# SWITCHES.net
KiCad netlist of a schematic drawn in Altium Designer
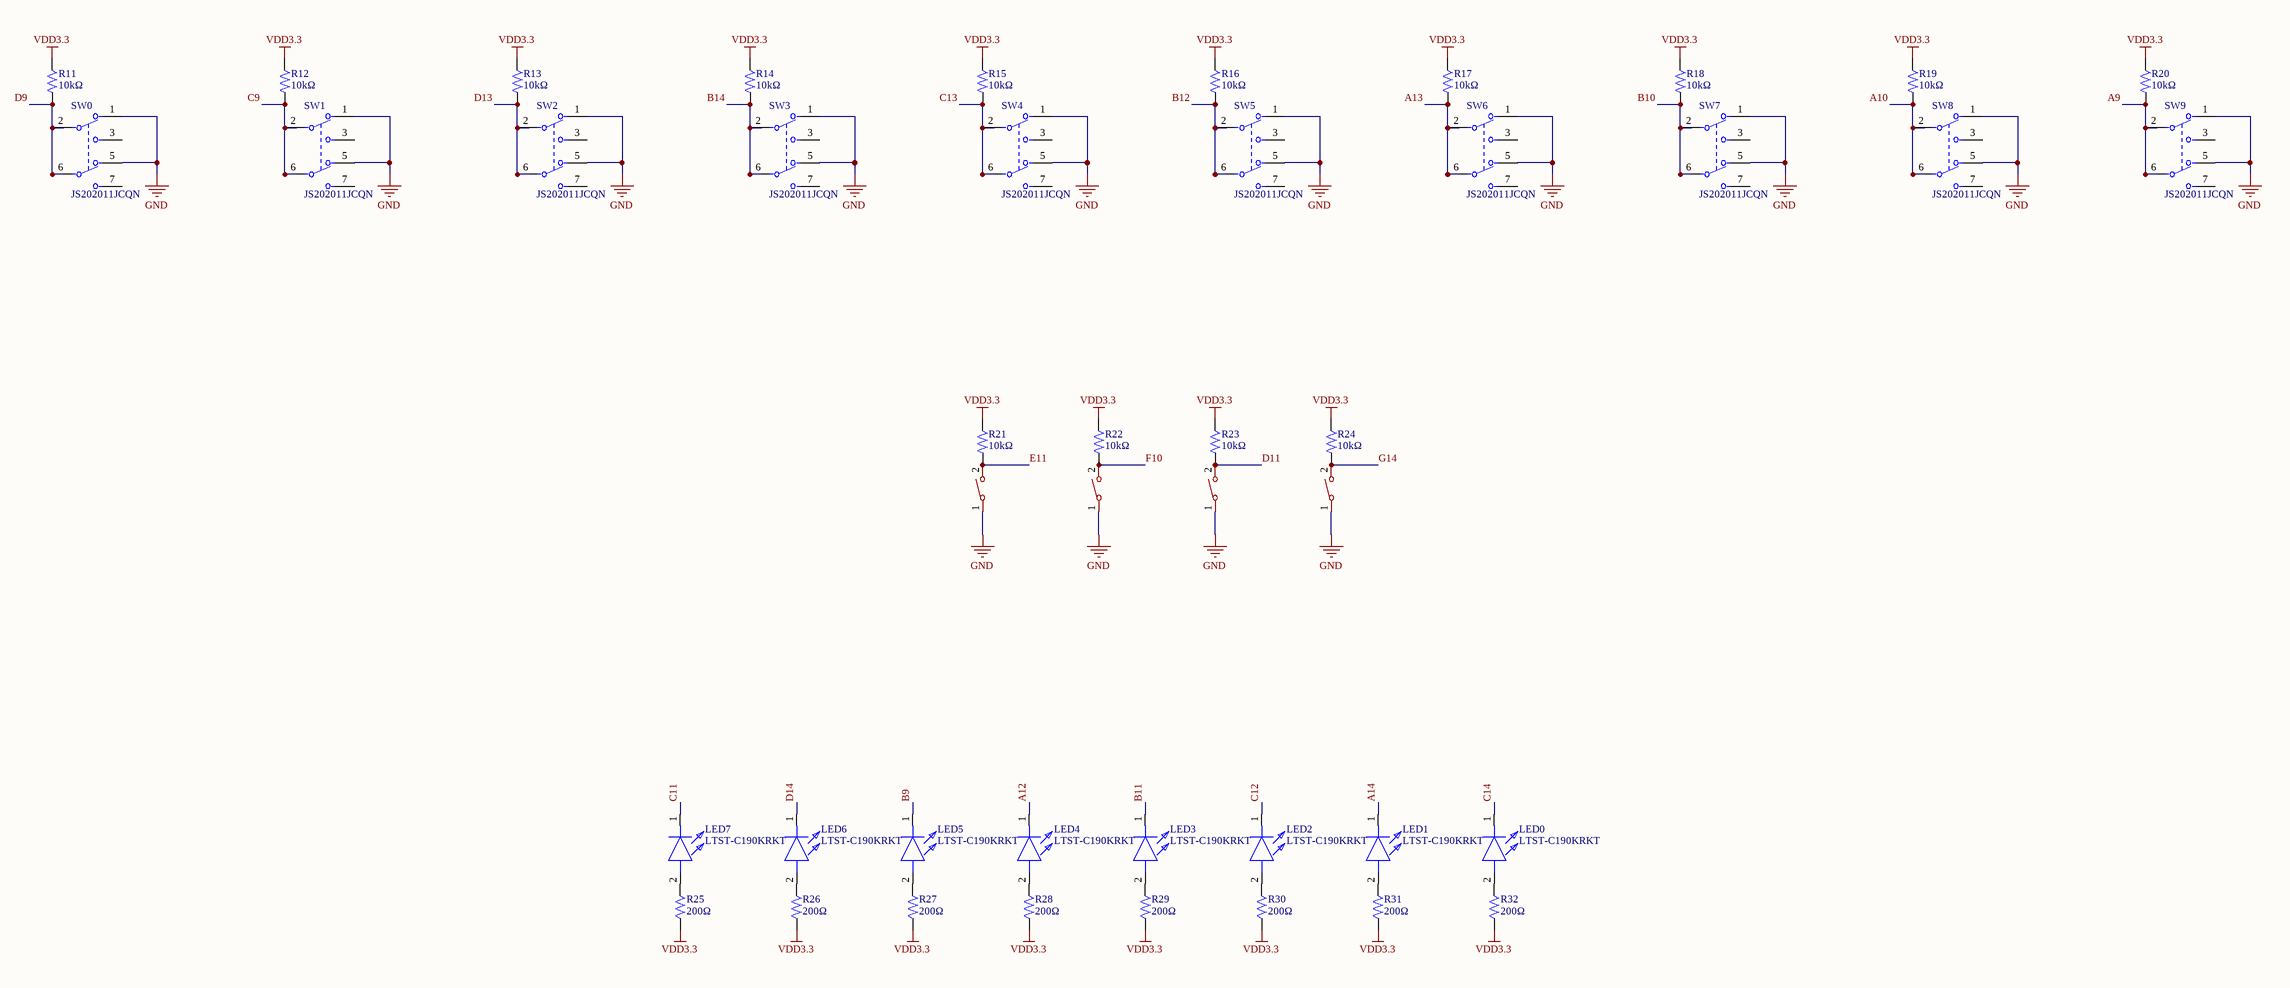
[diagram p0: SWITCHES.SchDoc]

(export (version "E")
  (design (tool "Eeschema 10.0.6"))
  (components
    (comp (ref "LED0")
      (value "LTST-C190KRKT")
      (footprint "SamacSys:LEDC1608X80N")
      (description "LED")
      (fields (field (name "MOUSER PART NUMBER") "859-LTST-C190KRKT"))
      (libsource (lib "*") (part "LTST-C190KRKT"))
    )
    (comp (ref "LED1")
      (value "LTST-C190KRKT")
      (footprint "SamacSys:LEDC1608X80N")
      (description "LED")
      (fields (field (name "MOUSER PART NUMBER") "859-LTST-C190KRKT"))
      (libsource (lib "*") (part "LTST-C190KRKT"))
    )
    (comp (ref "LED2")
      (value "LTST-C190KRKT")
      (footprint "SamacSys:LEDC1608X80N")
      (description "LED")
      (fields (field (name "MOUSER PART NUMBER") "859-LTST-C190KRKT"))
      (libsource (lib "*") (part "LTST-C190KRKT"))
    )
    (comp (ref "LED3")
      (value "LTST-C190KRKT")
      (footprint "SamacSys:LEDC1608X80N")
      (description "LED")
      (fields (field (name "MOUSER PART NUMBER") "859-LTST-C190KRKT"))
      (libsource (lib "*") (part "LTST-C190KRKT"))
    )
    (comp (ref "LED4")
      (value "LTST-C190KRKT")
      (footprint "SamacSys:LEDC1608X80N")
      (description "LED")
      (fields (field (name "MOUSER PART NUMBER") "859-LTST-C190KRKT"))
      (libsource (lib "*") (part "LTST-C190KRKT"))
    )
    (comp (ref "LED5")
      (value "LTST-C190KRKT")
      (footprint "SamacSys:LEDC1608X80N")
      (description "LED")
      (fields (field (name "MOUSER PART NUMBER") "859-LTST-C190KRKT"))
      (libsource (lib "*") (part "LTST-C190KRKT"))
    )
    (comp (ref "LED6")
      (value "LTST-C190KRKT")
      (footprint "SamacSys:LEDC1608X80N")
      (description "LED")
      (fields (field (name "MOUSER PART NUMBER") "859-LTST-C190KRKT"))
      (libsource (lib "*") (part "LTST-C190KRKT"))
    )
    (comp (ref "LED7")
      (value "LTST-C190KRKT")
      (footprint "SamacSys:LEDC1608X80N")
      (description "LED")
      (fields (field (name "MOUSER PART NUMBER") "859-LTST-C190KRKT"))
      (libsource (lib "*") (part "LTST-C190KRKT"))
    )
    (comp (ref "R11")
      (value "0603WAF1002T5E")
      (footprint "RES-0603")
      (description "Resistor, 10kΩ, ±1%, 100mW, 75V, ±100ppm/℃, -55℃~+155℃, SMD 0603")
      (fields
        (field (name "MANUFACTURER") "Uniroyal")
        (field (name "JLCPCB PART NUMBER") "C25804")
        (field (name "RESISTANCE") "10kΩ")
      )
      (libsource (lib "jlcpcb_2025_04_resistors_basic") (part "0603WAF1002T5E"))
    )
    (comp (ref "R12")
      (value "0603WAF1002T5E")
      (footprint "RES-0603")
      (description "Resistor, 10kΩ, ±1%, 100mW, 75V, ±100ppm/℃, -55℃~+155℃, SMD 0603")
      (fields
        (field (name "MANUFACTURER") "Uniroyal")
        (field (name "JLCPCB PART NUMBER") "C25804")
        (field (name "RESISTANCE") "10kΩ")
      )
      (libsource (lib "jlcpcb_2025_04_resistors_basic") (part "0603WAF1002T5E"))
    )
    (comp (ref "R13")
      (value "0603WAF1002T5E")
      (footprint "RES-0603")
      (description "Resistor, 10kΩ, ±1%, 100mW, 75V, ±100ppm/℃, -55℃~+155℃, SMD 0603")
      (fields
        (field (name "MANUFACTURER") "Uniroyal")
        (field (name "JLCPCB PART NUMBER") "C25804")
        (field (name "RESISTANCE") "10kΩ")
      )
      (libsource (lib "jlcpcb_2025_04_resistors_basic") (part "0603WAF1002T5E"))
    )
    (comp (ref "R14")
      (value "0603WAF1002T5E")
      (footprint "RES-0603")
      (description "Resistor, 10kΩ, ±1%, 100mW, 75V, ±100ppm/℃, -55℃~+155℃, SMD 0603")
      (fields
        (field (name "MANUFACTURER") "Uniroyal")
        (field (name "JLCPCB PART NUMBER") "C25804")
        (field (name "RESISTANCE") "10kΩ")
      )
      (libsource (lib "jlcpcb_2025_04_resistors_basic") (part "0603WAF1002T5E"))
    )
    (comp (ref "R15")
      (value "0603WAF1002T5E")
      (footprint "RES-0603")
      (description "Resistor, 10kΩ, ±1%, 100mW, 75V, ±100ppm/℃, -55℃~+155℃, SMD 0603")
      (fields
        (field (name "MANUFACTURER") "Uniroyal")
        (field (name "JLCPCB PART NUMBER") "C25804")
        (field (name "RESISTANCE") "10kΩ")
      )
      (libsource (lib "jlcpcb_2025_04_resistors_basic") (part "0603WAF1002T5E"))
    )
    (comp (ref "R16")
      (value "0603WAF1002T5E")
      (footprint "RES-0603")
      (description "Resistor, 10kΩ, ±1%, 100mW, 75V, ±100ppm/℃, -55℃~+155℃, SMD 0603")
      (fields
        (field (name "MANUFACTURER") "Uniroyal")
        (field (name "JLCPCB PART NUMBER") "C25804")
        (field (name "RESISTANCE") "10kΩ")
      )
      (libsource (lib "jlcpcb_2025_04_resistors_basic") (part "0603WAF1002T5E"))
    )
    (comp (ref "R17")
      (value "0603WAF1002T5E")
      (footprint "RES-0603")
      (description "Resistor, 10kΩ, ±1%, 100mW, 75V, ±100ppm/℃, -55℃~+155℃, SMD 0603")
      (fields
        (field (name "MANUFACTURER") "Uniroyal")
        (field (name "JLCPCB PART NUMBER") "C25804")
        (field (name "RESISTANCE") "10kΩ")
      )
      (libsource (lib "jlcpcb_2025_04_resistors_basic") (part "0603WAF1002T5E"))
    )
    (comp (ref "R18")
      (value "0603WAF1002T5E")
      (footprint "RES-0603")
      (description "Resistor, 10kΩ, ±1%, 100mW, 75V, ±100ppm/℃, -55℃~+155℃, SMD 0603")
      (fields
        (field (name "MANUFACTURER") "Uniroyal")
        (field (name "JLCPCB PART NUMBER") "C25804")
        (field (name "RESISTANCE") "10kΩ")
      )
      (libsource (lib "jlcpcb_2025_04_resistors_basic") (part "0603WAF1002T5E"))
    )
    (comp (ref "R19")
      (value "0603WAF1002T5E")
      (footprint "RES-0603")
      (description "Resistor, 10kΩ, ±1%, 100mW, 75V, ±100ppm/℃, -55℃~+155℃, SMD 0603")
      (fields
        (field (name "MANUFACTURER") "Uniroyal")
        (field (name "JLCPCB PART NUMBER") "C25804")
        (field (name "RESISTANCE") "10kΩ")
      )
      (libsource (lib "jlcpcb_2025_04_resistors_basic") (part "0603WAF1002T5E"))
    )
    (comp (ref "R20")
      (value "0603WAF1002T5E")
      (footprint "RES-0603")
      (description "Resistor, 10kΩ, ±1%, 100mW, 75V, ±100ppm/℃, -55℃~+155℃, SMD 0603")
      (fields
        (field (name "MANUFACTURER") "Uniroyal")
        (field (name "JLCPCB PART NUMBER") "C25804")
        (field (name "RESISTANCE") "10kΩ")
      )
      (libsource (lib "jlcpcb_2025_04_resistors_basic") (part "0603WAF1002T5E"))
    )
    (comp (ref "R21")
      (value "0603WAF1002T5E")
      (footprint "RES-0603")
      (description "Resistor, 10kΩ, ±1%, 100mW, 75V, ±100ppm/℃, -55℃~+155℃, SMD 0603")
      (fields
        (field (name "MANUFACTURER") "Uniroyal")
        (field (name "JLCPCB PART NUMBER") "C25804")
        (field (name "RESISTANCE") "10kΩ")
      )
      (libsource (lib "jlcpcb_2025_04_resistors_basic") (part "0603WAF1002T5E"))
    )
    (comp (ref "R22")
      (value "0603WAF1002T5E")
      (footprint "RES-0603")
      (description "Resistor, 10kΩ, ±1%, 100mW, 75V, ±100ppm/℃, -55℃~+155℃, SMD 0603")
      (fields
        (field (name "MANUFACTURER") "Uniroyal")
        (field (name "JLCPCB PART NUMBER") "C25804")
        (field (name "RESISTANCE") "10kΩ")
      )
      (libsource (lib "jlcpcb_2025_04_resistors_basic") (part "0603WAF1002T5E"))
    )
    (comp (ref "R23")
      (value "0603WAF1002T5E")
      (footprint "RES-0603")
      (description "Resistor, 10kΩ, ±1%, 100mW, 75V, ±100ppm/℃, -55℃~+155℃, SMD 0603")
      (fields
        (field (name "MANUFACTURER") "Uniroyal")
        (field (name "JLCPCB PART NUMBER") "C25804")
        (field (name "RESISTANCE") "10kΩ")
      )
      (libsource (lib "jlcpcb_2025_04_resistors_basic") (part "0603WAF1002T5E"))
    )
    (comp (ref "R24")
      (value "0603WAF1002T5E")
      (footprint "RES-0603")
      (description "Resistor, 10kΩ, ±1%, 100mW, 75V, ±100ppm/℃, -55℃~+155℃, SMD 0603")
      (fields
        (field (name "MANUFACTURER") "Uniroyal")
        (field (name "JLCPCB PART NUMBER") "C25804")
        (field (name "RESISTANCE") "10kΩ")
      )
      (libsource (lib "jlcpcb_2025_04_resistors_basic") (part "0603WAF1002T5E"))
    )
    (comp (ref "R25")
      (value "0402WGF2000TCE")
      (footprint "RES-0402")
      (description "Resistor, 200Ω, ±1%, 62.5mW, 50V, ±100ppm/℃, -55℃~+155℃, SMD 0402")
      (fields
        (field (name "MANUFACTURER") "Uniroyal")
        (field (name "JLCPCB PART NUMBER") "C25087")
        (field (name "RESISTANCE") "200Ω")
      )
      (libsource (lib "jlcpcb_2025_04_resistors_basic") (part "0402WGF2000TCE"))
    )
    (comp (ref "R26")
      (value "0402WGF2000TCE")
      (footprint "RES-0402")
      (description "Resistor, 200Ω, ±1%, 62.5mW, 50V, ±100ppm/℃, -55℃~+155℃, SMD 0402")
      (fields
        (field (name "MANUFACTURER") "Uniroyal")
        (field (name "JLCPCB PART NUMBER") "C25087")
        (field (name "RESISTANCE") "200Ω")
      )
      (libsource (lib "jlcpcb_2025_04_resistors_basic") (part "0402WGF2000TCE"))
    )
    (comp (ref "R27")
      (value "0402WGF2000TCE")
      (footprint "RES-0402")
      (description "Resistor, 200Ω, ±1%, 62.5mW, 50V, ±100ppm/℃, -55℃~+155℃, SMD 0402")
      (fields
        (field (name "MANUFACTURER") "Uniroyal")
        (field (name "JLCPCB PART NUMBER") "C25087")
        (field (name "RESISTANCE") "200Ω")
      )
      (libsource (lib "jlcpcb_2025_04_resistors_basic") (part "0402WGF2000TCE"))
    )
    (comp (ref "R28")
      (value "0402WGF2000TCE")
      (footprint "RES-0402")
      (description "Resistor, 200Ω, ±1%, 62.5mW, 50V, ±100ppm/℃, -55℃~+155℃, SMD 0402")
      (fields
        (field (name "MANUFACTURER") "Uniroyal")
        (field (name "JLCPCB PART NUMBER") "C25087")
        (field (name "RESISTANCE") "200Ω")
      )
      (libsource (lib "jlcpcb_2025_04_resistors_basic") (part "0402WGF2000TCE"))
    )
    (comp (ref "R29")
      (value "0402WGF2000TCE")
      (footprint "RES-0402")
      (description "Resistor, 200Ω, ±1%, 62.5mW, 50V, ±100ppm/℃, -55℃~+155℃, SMD 0402")
      (fields
        (field (name "MANUFACTURER") "Uniroyal")
        (field (name "JLCPCB PART NUMBER") "C25087")
        (field (name "RESISTANCE") "200Ω")
      )
      (libsource (lib "jlcpcb_2025_04_resistors_basic") (part "0402WGF2000TCE"))
    )
    (comp (ref "R30")
      (value "0402WGF2000TCE")
      (footprint "RES-0402")
      (description "Resistor, 200Ω, ±1%, 62.5mW, 50V, ±100ppm/℃, -55℃~+155℃, SMD 0402")
      (fields
        (field (name "MANUFACTURER") "Uniroyal")
        (field (name "JLCPCB PART NUMBER") "C25087")
        (field (name "RESISTANCE") "200Ω")
      )
      (libsource (lib "jlcpcb_2025_04_resistors_basic") (part "0402WGF2000TCE"))
    )
    (comp (ref "R31")
      (value "0402WGF2000TCE")
      (footprint "RES-0402")
      (description "Resistor, 200Ω, ±1%, 62.5mW, 50V, ±100ppm/℃, -55℃~+155℃, SMD 0402")
      (fields
        (field (name "MANUFACTURER") "Uniroyal")
        (field (name "JLCPCB PART NUMBER") "C25087")
        (field (name "RESISTANCE") "200Ω")
      )
      (libsource (lib "jlcpcb_2025_04_resistors_basic") (part "0402WGF2000TCE"))
    )
    (comp (ref "R32")
      (value "0402WGF2000TCE")
      (footprint "RES-0402")
      (description "Resistor, 200Ω, ±1%, 62.5mW, 50V, ±100ppm/℃, -55℃~+155℃, SMD 0402")
      (fields
        (field (name "MANUFACTURER") "Uniroyal")
        (field (name "JLCPCB PART NUMBER") "C25087")
        (field (name "RESISTANCE") "200Ω")
      )
      (libsource (lib "jlcpcb_2025_04_resistors_basic") (part "0402WGF2000TCE"))
    )
    (comp (ref "SW0")
      (value "JS202011JCQN")
      (footprint "FP-JS202011JCQN-MFG")
      (description "SWITCH SLIDE DPDT 300MA 6V")
      (libsource (lib "Altium Content Vault") (part "6b3bc4f94d389b2e45f6181d1f21823"))
    )
    (comp (ref "SW1")
      (value "JS202011JCQN")
      (footprint "FP-JS202011JCQN-MFG")
      (description "SWITCH SLIDE DPDT 300MA 6V")
      (libsource (lib "Altium Content Vault") (part "6b3bc4f94d389b2e45f6181d1f21823"))
    )
    (comp (ref "SW2")
      (value "JS202011JCQN")
      (footprint "FP-JS202011JCQN-MFG")
      (description "SWITCH SLIDE DPDT 300MA 6V")
      (libsource (lib "Altium Content Vault") (part "6b3bc4f94d389b2e45f6181d1f21823"))
    )
    (comp (ref "SW3")
      (value "JS202011JCQN")
      (footprint "FP-JS202011JCQN-MFG")
      (description "SWITCH SLIDE DPDT 300MA 6V")
      (libsource (lib "Altium Content Vault") (part "6b3bc4f94d389b2e45f6181d1f21823"))
    )
    (comp (ref "SW4")
      (value "JS202011JCQN")
      (footprint "FP-JS202011JCQN-MFG")
      (description "SWITCH SLIDE DPDT 300MA 6V")
      (libsource (lib "Altium Content Vault") (part "6b3bc4f94d389b2e45f6181d1f21823"))
    )
    (comp (ref "SW5")
      (value "JS202011JCQN")
      (footprint "FP-JS202011JCQN-MFG")
      (description "SWITCH SLIDE DPDT 300MA 6V")
      (libsource (lib "Altium Content Vault") (part "6b3bc4f94d389b2e45f6181d1f21823"))
    )
    (comp (ref "SW6")
      (value "JS202011JCQN")
      (footprint "FP-JS202011JCQN-MFG")
      (description "SWITCH SLIDE DPDT 300MA 6V")
      (libsource (lib "Altium Content Vault") (part "6b3bc4f94d389b2e45f6181d1f21823"))
    )
    (comp (ref "SW7")
      (value "JS202011JCQN")
      (footprint "FP-JS202011JCQN-MFG")
      (description "SWITCH SLIDE DPDT 300MA 6V")
      (libsource (lib "Altium Content Vault") (part "6b3bc4f94d389b2e45f6181d1f21823"))
    )
    (comp (ref "SW8")
      (value "JS202011JCQN")
      (footprint "FP-JS202011JCQN-MFG")
      (description "SWITCH SLIDE DPDT 300MA 6V")
      (libsource (lib "Altium Content Vault") (part "6b3bc4f94d389b2e45f6181d1f21823"))
    )
    (comp (ref "SW9")
      (value "JS202011JCQN")
      (footprint "FP-JS202011JCQN-MFG")
      (description "SWITCH SLIDE DPDT 300MA 6V")
      (libsource (lib "Altium Content Vault") (part "6b3bc4f94d389b2e45f6181d1f21823"))
    )
    (comp (ref "SW10")
      (value "TS-1185-B-A-B-A")
      (footprint "TS-1185-B-A-B-A")
      (description "Tactile switch ROHS, SPST Surface Mount, -30C +85C 1.6N 12V 2mm 3mm 4mm 50mA Black no round button")
      (fields (field (name "MANUFACTURER") "XKB Connectivity(中国星坤)"))
      (libsource (lib "Schlib1") (part "TS-1185-B-A-B-A"))
    )
    (comp (ref "SW11")
      (value "TS-1185-B-A-B-A")
      (footprint "TS-1185-B-A-B-A")
      (description "Tactile switch ROHS, SPST Surface Mount, -30C +85C 1.6N 12V 2mm 3mm 4mm 50mA Black no round button")
      (fields (field (name "MANUFACTURER") "XKB Connectivity(中国星坤)"))
      (libsource (lib "Schlib1") (part "TS-1185-B-A-B-A"))
    )
    (comp (ref "SW12")
      (value "TS-1185-B-A-B-A")
      (footprint "TS-1185-B-A-B-A")
      (description "Tactile switch ROHS, SPST Surface Mount, -30C +85C 1.6N 12V 2mm 3mm 4mm 50mA Black no round button")
      (fields (field (name "MANUFACTURER") "XKB Connectivity(中国星坤)"))
      (libsource (lib "Schlib1") (part "TS-1185-B-A-B-A"))
    )
    (comp (ref "SW13")
      (value "TS-1185-B-A-B-A")
      (footprint "TS-1185-B-A-B-A")
      (description "Tactile switch ROHS, SPST Surface Mount, -30C +85C 1.6N 12V 2mm 3mm 4mm 50mA Black no round button")
      (fields (field (name "MANUFACTURER") "XKB Connectivity(中国星坤)"))
      (libsource (lib "Schlib1") (part "TS-1185-B-A-B-A"))
    )
  )
  (nets
    (net (code "1") (name "/A9") (class "Default")
      (node (ref "R20") (pin "1") (pinfunction "1_1") (pintype "passive"))
      (node (ref "SW9") (pin "2") (pinfunction "1_C_2") (pintype "passive"))
      (node (ref "SW9") (pin "6") (pinfunction "2_C_6") (pintype "passive"))
    )
    (net (code "2") (name "/A10") (class "Default")
      (node (ref "R19") (pin "1") (pinfunction "1_1") (pintype "passive"))
      (node (ref "SW8") (pin "2") (pinfunction "1_C_2") (pintype "passive"))
      (node (ref "SW8") (pin "6") (pinfunction "2_C_6") (pintype "passive"))
    )
    (net (code "3") (name "/A12") (class "Default")
      (node (ref "LED4") (pin "1") (pinfunction "K_1") (pintype "passive"))
    )
    (net (code "4") (name "/A13") (class "Default")
      (node (ref "R17") (pin "1") (pinfunction "1_1") (pintype "passive"))
      (node (ref "SW6") (pin "2") (pinfunction "1_C_2") (pintype "passive"))
      (node (ref "SW6") (pin "6") (pinfunction "2_C_6") (pintype "passive"))
    )
    (net (code "5") (name "/A14") (class "Default")
      (node (ref "LED1") (pin "1") (pinfunction "K_1") (pintype "passive"))
    )
    (net (code "6") (name "/B9") (class "Default")
      (node (ref "LED5") (pin "1") (pinfunction "K_1") (pintype "passive"))
    )
    (net (code "7") (name "/B10") (class "Default")
      (node (ref "R18") (pin "1") (pinfunction "1_1") (pintype "passive"))
      (node (ref "SW7") (pin "2") (pinfunction "1_C_2") (pintype "passive"))
      (node (ref "SW7") (pin "6") (pinfunction "2_C_6") (pintype "passive"))
    )
    (net (code "8") (name "/B11") (class "Default")
      (node (ref "LED3") (pin "1") (pinfunction "K_1") (pintype "passive"))
    )
    (net (code "9") (name "/B12") (class "Default")
      (node (ref "R16") (pin "1") (pinfunction "1_1") (pintype "passive"))
      (node (ref "SW5") (pin "2") (pinfunction "1_C_2") (pintype "passive"))
      (node (ref "SW5") (pin "6") (pinfunction "2_C_6") (pintype "passive"))
    )
    (net (code "10") (name "/B14") (class "Default")
      (node (ref "R14") (pin "1") (pinfunction "1_1") (pintype "passive"))
      (node (ref "SW3") (pin "2") (pinfunction "1_C_2") (pintype "passive"))
      (node (ref "SW3") (pin "6") (pinfunction "2_C_6") (pintype "passive"))
    )
    (net (code "11") (name "/C9") (class "Default")
      (node (ref "R12") (pin "1") (pinfunction "1_1") (pintype "passive"))
      (node (ref "SW1") (pin "2") (pinfunction "1_C_2") (pintype "passive"))
      (node (ref "SW1") (pin "6") (pinfunction "2_C_6") (pintype "passive"))
    )
    (net (code "12") (name "/C11") (class "Default")
      (node (ref "LED7") (pin "1") (pinfunction "K_1") (pintype "passive"))
    )
    (net (code "13") (name "/C12") (class "Default")
      (node (ref "LED2") (pin "1") (pinfunction "K_1") (pintype "passive"))
    )
    (net (code "14") (name "/C13") (class "Default")
      (node (ref "R15") (pin "1") (pinfunction "1_1") (pintype "passive"))
      (node (ref "SW4") (pin "2") (pinfunction "1_C_2") (pintype "passive"))
      (node (ref "SW4") (pin "6") (pinfunction "2_C_6") (pintype "passive"))
    )
    (net (code "15") (name "/C14") (class "Default")
      (node (ref "LED0") (pin "1") (pinfunction "K_1") (pintype "passive"))
    )
    (net (code "16") (name "/D9") (class "Default")
      (node (ref "R11") (pin "1") (pinfunction "1_1") (pintype "passive"))
      (node (ref "SW0") (pin "2") (pinfunction "1_C_2") (pintype "passive"))
      (node (ref "SW0") (pin "6") (pinfunction "2_C_6") (pintype "passive"))
    )
    (net (code "17") (name "/D11") (class "Default")
      (node (ref "R23") (pin "1") (pinfunction "1_1") (pintype "passive"))
      (node (ref "SW12") (pin "2") (pinfunction "2_2") (pintype "passive"))
    )
    (net (code "18") (name "/D13") (class "Default")
      (node (ref "R13") (pin "1") (pinfunction "1_1") (pintype "passive"))
      (node (ref "SW2") (pin "2") (pinfunction "1_C_2") (pintype "passive"))
      (node (ref "SW2") (pin "6") (pinfunction "2_C_6") (pintype "passive"))
    )
    (net (code "19") (name "/D14") (class "Default")
      (node (ref "LED6") (pin "1") (pinfunction "K_1") (pintype "passive"))
    )
    (net (code "20") (name "/E11") (class "Default")
      (node (ref "R21") (pin "1") (pinfunction "1_1") (pintype "passive"))
      (node (ref "SW10") (pin "2") (pinfunction "2_2") (pintype "passive"))
    )
    (net (code "21") (name "/F10") (class "Default")
      (node (ref "R22") (pin "1") (pinfunction "1_1") (pintype "passive"))
      (node (ref "SW11") (pin "2") (pinfunction "2_2") (pintype "passive"))
    )
    (net (code "22") (name "/G14") (class "Default")
      (node (ref "R24") (pin "1") (pinfunction "1_1") (pintype "passive"))
      (node (ref "SW13") (pin "2") (pinfunction "2_2") (pintype "passive"))
    )
    (net (code "23") (name "GND") (class "Default")
      (node (ref "SW0") (pin "1") (pinfunction "1_1") (pintype "passive"))
      (node (ref "SW0") (pin "5") (pinfunction "5_5") (pintype "passive"))
      (node (ref "SW1") (pin "1") (pinfunction "1_1") (pintype "passive"))
      (node (ref "SW1") (pin "5") (pinfunction "5_5") (pintype "passive"))
      (node (ref "SW10") (pin "1") (pinfunction "1_1") (pintype "passive"))
      (node (ref "SW11") (pin "1") (pinfunction "1_1") (pintype "passive"))
      (node (ref "SW12") (pin "1") (pinfunction "1_1") (pintype "passive"))
      (node (ref "SW13") (pin "1") (pinfunction "1_1") (pintype "passive"))
      (node (ref "SW2") (pin "1") (pinfunction "1_1") (pintype "passive"))
      (node (ref "SW2") (pin "5") (pinfunction "5_5") (pintype "passive"))
      (node (ref "SW3") (pin "1") (pinfunction "1_1") (pintype "passive"))
      (node (ref "SW3") (pin "5") (pinfunction "5_5") (pintype "passive"))
      (node (ref "SW4") (pin "1") (pinfunction "1_1") (pintype "passive"))
      (node (ref "SW4") (pin "5") (pinfunction "5_5") (pintype "passive"))
      (node (ref "SW5") (pin "1") (pinfunction "1_1") (pintype "passive"))
      (node (ref "SW5") (pin "5") (pinfunction "5_5") (pintype "passive"))
      (node (ref "SW6") (pin "1") (pinfunction "1_1") (pintype "passive"))
      (node (ref "SW6") (pin "5") (pinfunction "5_5") (pintype "passive"))
      (node (ref "SW7") (pin "1") (pinfunction "1_1") (pintype "passive"))
      (node (ref "SW7") (pin "5") (pinfunction "5_5") (pintype "passive"))
      (node (ref "SW8") (pin "1") (pinfunction "1_1") (pintype "passive"))
      (node (ref "SW8") (pin "5") (pinfunction "5_5") (pintype "passive"))
      (node (ref "SW9") (pin "1") (pinfunction "1_1") (pintype "passive"))
      (node (ref "SW9") (pin "5") (pinfunction "5_5") (pintype "passive"))
    )
    (net (code "24") (name "Net-(LED0-A)") (class "Default")
      (node (ref "LED0") (pin "2") (pinfunction "A_2") (pintype "passive"))
      (node (ref "R32") (pin "2") (pinfunction "2_2") (pintype "passive"))
    )
    (net (code "25") (name "Net-(LED1-A)") (class "Default")
      (node (ref "LED1") (pin "2") (pinfunction "A_2") (pintype "passive"))
      (node (ref "R31") (pin "2") (pinfunction "2_2") (pintype "passive"))
    )
    (net (code "26") (name "Net-(LED2-A)") (class "Default")
      (node (ref "LED2") (pin "2") (pinfunction "A_2") (pintype "passive"))
      (node (ref "R30") (pin "2") (pinfunction "2_2") (pintype "passive"))
    )
    (net (code "27") (name "Net-(LED3-A)") (class "Default")
      (node (ref "LED3") (pin "2") (pinfunction "A_2") (pintype "passive"))
      (node (ref "R29") (pin "2") (pinfunction "2_2") (pintype "passive"))
    )
    (net (code "28") (name "Net-(LED4-A)") (class "Default")
      (node (ref "LED4") (pin "2") (pinfunction "A_2") (pintype "passive"))
      (node (ref "R28") (pin "2") (pinfunction "2_2") (pintype "passive"))
    )
    (net (code "29") (name "Net-(LED5-A)") (class "Default")
      (node (ref "LED5") (pin "2") (pinfunction "A_2") (pintype "passive"))
      (node (ref "R27") (pin "2") (pinfunction "2_2") (pintype "passive"))
    )
    (net (code "30") (name "Net-(LED6-A)") (class "Default")
      (node (ref "LED6") (pin "2") (pinfunction "A_2") (pintype "passive"))
      (node (ref "R26") (pin "2") (pinfunction "2_2") (pintype "passive"))
    )
    (net (code "31") (name "Net-(LED7-A)") (class "Default")
      (node (ref "LED7") (pin "2") (pinfunction "A_2") (pintype "passive"))
      (node (ref "R25") (pin "2") (pinfunction "2_2") (pintype "passive"))
    )
    (net (code "32") (name "VDD3.3") (class "Default")
      (node (ref "R11") (pin "2") (pinfunction "2_2") (pintype "passive"))
      (node (ref "R12") (pin "2") (pinfunction "2_2") (pintype "passive"))
      (node (ref "R13") (pin "2") (pinfunction "2_2") (pintype "passive"))
      (node (ref "R14") (pin "2") (pinfunction "2_2") (pintype "passive"))
      (node (ref "R15") (pin "2") (pinfunction "2_2") (pintype "passive"))
      (node (ref "R16") (pin "2") (pinfunction "2_2") (pintype "passive"))
      (node (ref "R17") (pin "2") (pinfunction "2_2") (pintype "passive"))
      (node (ref "R18") (pin "2") (pinfunction "2_2") (pintype "passive"))
      (node (ref "R19") (pin "2") (pinfunction "2_2") (pintype "passive"))
      (node (ref "R20") (pin "2") (pinfunction "2_2") (pintype "passive"))
      (node (ref "R21") (pin "2") (pinfunction "2_2") (pintype "passive"))
      (node (ref "R22") (pin "2") (pinfunction "2_2") (pintype "passive"))
      (node (ref "R23") (pin "2") (pinfunction "2_2") (pintype "passive"))
      (node (ref "R24") (pin "2") (pinfunction "2_2") (pintype "passive"))
      (node (ref "R25") (pin "1") (pinfunction "1_1") (pintype "passive"))
      (node (ref "R26") (pin "1") (pinfunction "1_1") (pintype "passive"))
      (node (ref "R27") (pin "1") (pinfunction "1_1") (pintype "passive"))
      (node (ref "R28") (pin "1") (pinfunction "1_1") (pintype "passive"))
      (node (ref "R29") (pin "1") (pinfunction "1_1") (pintype "passive"))
      (node (ref "R30") (pin "1") (pinfunction "1_1") (pintype "passive"))
      (node (ref "R31") (pin "1") (pinfunction "1_1") (pintype "passive"))
      (node (ref "R32") (pin "1") (pinfunction "1_1") (pintype "passive"))
    )
    (net (code "33") (name "unconnected-(SW0-Pad3)") (class "Default")
      (node (ref "SW0") (pin "3") (pinfunction "3_3") (pintype "passive"))
    )
    (net (code "34") (name "unconnected-(SW0-Pad7)") (class "Default")
      (node (ref "SW0") (pin "7") (pinfunction "7_7") (pintype "passive"))
    )
    (net (code "35") (name "unconnected-(SW1-Pad3)") (class "Default")
      (node (ref "SW1") (pin "3") (pinfunction "3_3") (pintype "passive"))
    )
    (net (code "36") (name "unconnected-(SW1-Pad7)") (class "Default")
      (node (ref "SW1") (pin "7") (pinfunction "7_7") (pintype "passive"))
    )
    (net (code "37") (name "unconnected-(SW2-Pad3)") (class "Default")
      (node (ref "SW2") (pin "3") (pinfunction "3_3") (pintype "passive"))
    )
    (net (code "38") (name "unconnected-(SW2-Pad7)") (class "Default")
      (node (ref "SW2") (pin "7") (pinfunction "7_7") (pintype "passive"))
    )
    (net (code "39") (name "unconnected-(SW3-Pad3)") (class "Default")
      (node (ref "SW3") (pin "3") (pinfunction "3_3") (pintype "passive"))
    )
    (net (code "40") (name "unconnected-(SW3-Pad7)") (class "Default")
      (node (ref "SW3") (pin "7") (pinfunction "7_7") (pintype "passive"))
    )
    (net (code "41") (name "unconnected-(SW4-Pad3)") (class "Default")
      (node (ref "SW4") (pin "3") (pinfunction "3_3") (pintype "passive"))
    )
    (net (code "42") (name "unconnected-(SW4-Pad7)") (class "Default")
      (node (ref "SW4") (pin "7") (pinfunction "7_7") (pintype "passive"))
    )
    (net (code "43") (name "unconnected-(SW5-Pad3)") (class "Default")
      (node (ref "SW5") (pin "3") (pinfunction "3_3") (pintype "passive"))
    )
    (net (code "44") (name "unconnected-(SW5-Pad7)") (class "Default")
      (node (ref "SW5") (pin "7") (pinfunction "7_7") (pintype "passive"))
    )
    (net (code "45") (name "unconnected-(SW6-Pad3)") (class "Default")
      (node (ref "SW6") (pin "3") (pinfunction "3_3") (pintype "passive"))
    )
    (net (code "46") (name "unconnected-(SW6-Pad7)") (class "Default")
      (node (ref "SW6") (pin "7") (pinfunction "7_7") (pintype "passive"))
    )
    (net (code "47") (name "unconnected-(SW7-Pad3)") (class "Default")
      (node (ref "SW7") (pin "3") (pinfunction "3_3") (pintype "passive"))
    )
    (net (code "48") (name "unconnected-(SW7-Pad7)") (class "Default")
      (node (ref "SW7") (pin "7") (pinfunction "7_7") (pintype "passive"))
    )
    (net (code "49") (name "unconnected-(SW8-Pad3)") (class "Default")
      (node (ref "SW8") (pin "3") (pinfunction "3_3") (pintype "passive"))
    )
    (net (code "50") (name "unconnected-(SW8-Pad7)") (class "Default")
      (node (ref "SW8") (pin "7") (pinfunction "7_7") (pintype "passive"))
    )
    (net (code "51") (name "unconnected-(SW9-Pad3)") (class "Default")
      (node (ref "SW9") (pin "3") (pinfunction "3_3") (pintype "passive"))
    )
    (net (code "52") (name "unconnected-(SW9-Pad7)") (class "Default")
      (node (ref "SW9") (pin "7") (pinfunction "7_7") (pintype "passive"))
    )
  )
)
